# Canhbaochayrung.net
KiCad netlist of a schematic drawn in Altium Designer
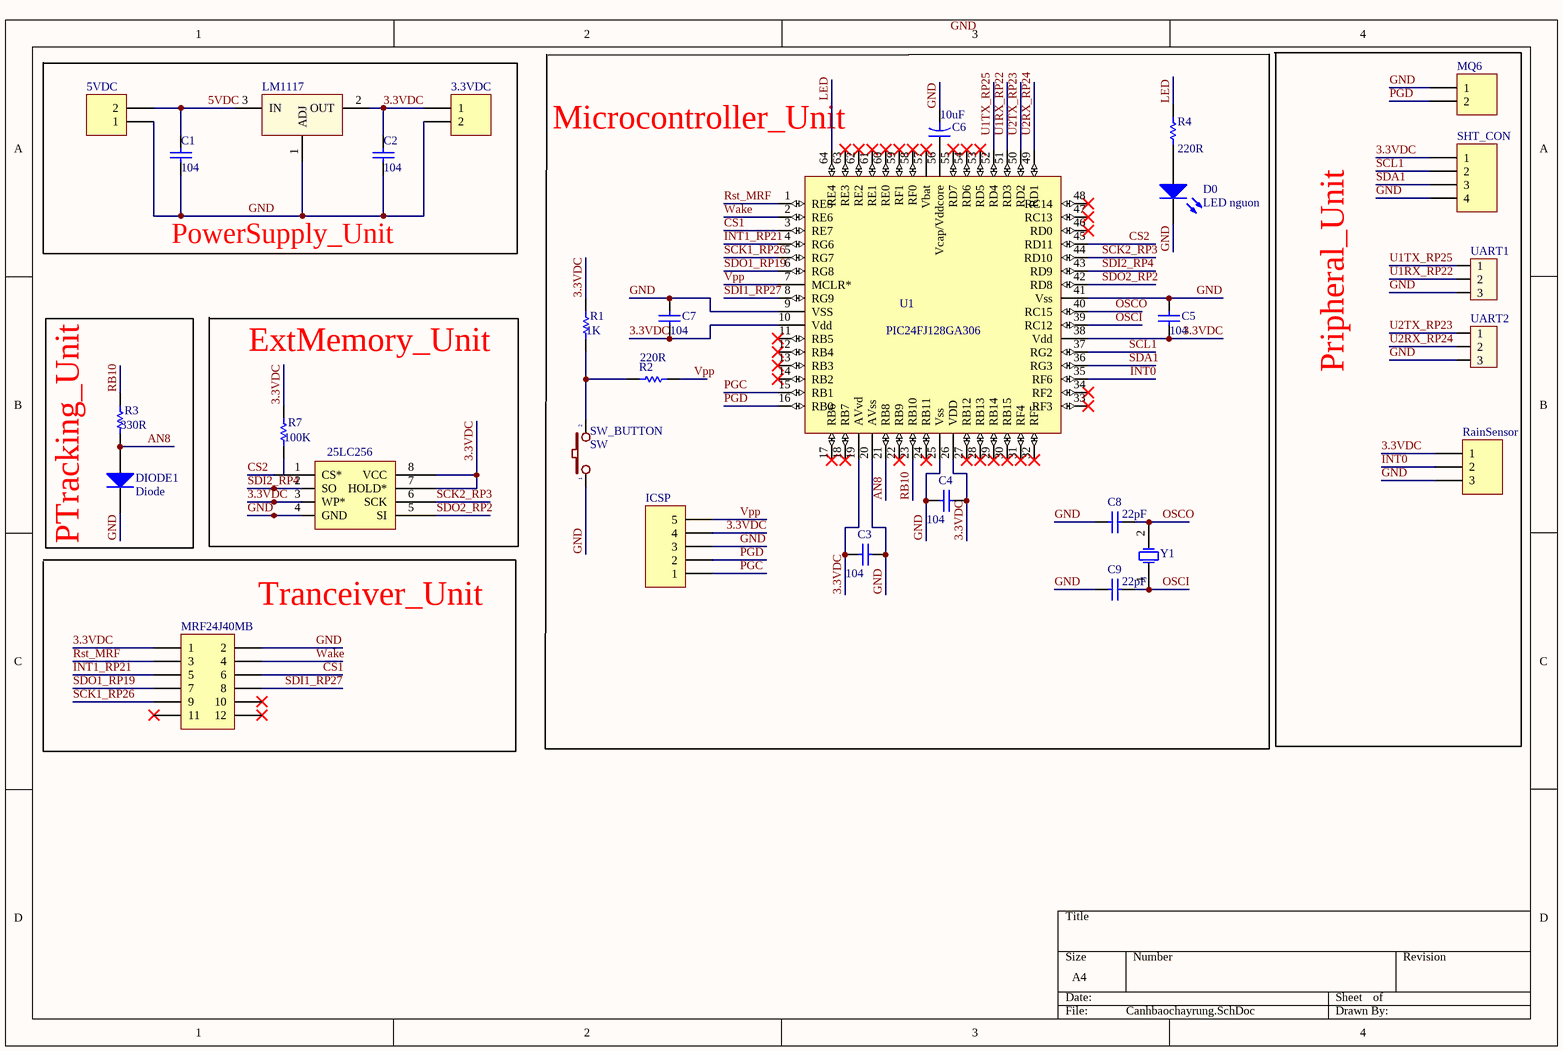
[diagram p0: Canhbaochayrung.SchDoc]

(export (version "E")
  (design (tool "Eeschema 10.0.6"))
  (components
    (comp (ref "3.3VDC")
      (value "Header 2")
      (footprint "HDR1X2")
      (description "Header, 2-Pin")
      (fields (field (name "PUBLISHER") "Altium Limited"))
      (libsource (lib "") (part "Header 2_1"))
    )
    (comp (ref "5VDC")
      (value "Header 2")
      (footprint "HDR1X2")
      (description "Header, 2-Pin")
      (fields (field (name "PUBLISHER") "Altium Limited"))
      (libsource (lib "Miscellaneous Connectors") (part "Header 2"))
    )
    (comp (ref "25LC256") (value "25LC256") (footprint "DIP-8") (libsource (lib "25LC256") (part "25LC256")))
    (comp (ref "C1")
      (value "104")
      (footprint "C0805")
      (description "Capacitor")
      (fields (field (name "Comment") "Cap") (field (name "PUBLISHER") "Altium Limited"))
      (libsource (lib "Miscellaneous Devices") (part "Cap"))
    )
    (comp (ref "C2")
      (value "104")
      (footprint "C0805")
      (description "Capacitor")
      (fields (field (name "Comment") "Cap") (field (name "PUBLISHER") "Altium Limited"))
      (libsource (lib "Miscellaneous Devices") (part "Cap"))
    )
    (comp (ref "C3")
      (value "104")
      (footprint "C0805")
      (description "Capacitor")
      (fields (field (name "Comment") "Cap") (field (name "PUBLISHER") "Altium Limited"))
      (libsource (lib "Miscellaneous Devices") (part "Cap"))
    )
    (comp (ref "C4")
      (value "104")
      (footprint "C0805")
      (description "Capacitor")
      (fields (field (name "Comment") "Cap") (field (name "PUBLISHER") "Altium Limited"))
      (libsource (lib "Miscellaneous Devices") (part "Cap"))
    )
    (comp (ref "C5")
      (value "104")
      (footprint "C0805")
      (description "Capacitor")
      (fields (field (name "Comment") "Cap") (field (name "PUBLISHER") "Altium Limited"))
      (libsource (lib "Miscellaneous Devices") (part "Cap"))
    )
    (comp (ref "C6")
      (value "10uF")
      (footprint "CAP P 6.3x5.4")
      (description "Capacitor")
      (fields (field (name "Comment") "Cap2") (field (name "PUBLISHER") "Altium Limited"))
      (libsource (lib "Miscellaneous Devices") (part "Cap2"))
    )
    (comp (ref "C7")
      (value "104")
      (footprint "C0805")
      (description "Capacitor")
      (fields (field (name "Comment") "Cap") (field (name "PUBLISHER") "Altium Limited"))
      (libsource (lib "Miscellaneous Devices") (part "Cap"))
    )
    (comp (ref "C8")
      (value "22pF")
      (footprint "SM-0805")
      (description "Capacitor")
      (fields (field (name "Comment") "Cap") (field (name "PUBLISHER") "Altium Limited"))
      (libsource (lib "Miscellaneous Devices") (part "Cap"))
    )
    (comp (ref "C9")
      (value "22pF")
      (footprint "SM-0805")
      (description "Capacitor")
      (fields (field (name "Comment") "Cap") (field (name "PUBLISHER") "Altium Limited"))
      (libsource (lib "Miscellaneous Devices") (part "Cap"))
    )
    (comp (ref "D0")
      (value "LED nguon")
      (footprint "LED3mm")
      (description "Typical INFRARED GaAs LED")
      (fields (field (name "PUBLISHER") "Altium Limited"))
      (libsource (lib "Miscellaneous Devices") (part "LED0"))
    )
    (comp (ref "DIODE1")
      (value "Diode")
      (footprint "DZ0.5A")
      (description "Default Diode")
      (fields (field (name "PUBLISHER") "Altium Limited"))
      (libsource (lib "Miscellaneous Devices") (part "Diode"))
    )
    (comp (ref "ICSP")
      (value "ICSP")
      (footprint "CON5")
      (description "Header, 5-Pin")
      (fields (field (name "PUBLISHER") "Altium Limited"))
      (libsource (lib "Miscellaneous Connectors") (part "Header 5"))
    )
    (comp (ref "LM1117")
      (value "LM317")
      (footprint "SOT223-4N")
      (description "Adj Voltage +1.2 -> +37V")
      (libsource (lib "syhaunguyen") (part "LM317"))
    )
    (comp (ref "MQ6")
      (value "MQ-6")
      (footprint "CON2")
      (description "Header, 2-Pin")
      (fields (field (name "PUBLISHER") "Altium Limited"))
      (libsource (lib "") (part "Header 2_1"))
    )
    (comp (ref "MRF24J40MB")
      (value "Header 6X2")
      (footprint "MRF24J40MB_board_mini")
      (description "Header, 6-Pin, Dual row")
      (fields (field (name "PUBLISHER") "Altium Limited"))
      (libsource (lib "Miscellaneous Connectors") (part "Header 6X2"))
    )
    (comp (ref "R1")
      (value "1K")
      (footprint "C0805")
      (description "Resistor")
      (fields (field (name "Comment") "Res1") (field (name "PUBLISHER") "Altium Limited"))
      (libsource (lib "Miscellaneous Devices") (part "Res1"))
    )
    (comp (ref "R2")
      (value "220R")
      (footprint "C0805")
      (description "Resistor")
      (fields (field (name "Comment") "res") (field (name "PUBLISHER") "Altium Limited"))
      (libsource (lib "Miscellaneous Devices") (part "Res1"))
    )
    (comp (ref "R3")
      (value "330R")
      (footprint "C0805")
      (description "Resistor")
      (fields (field (name "Comment") "Res1") (field (name "PUBLISHER") "Altium Limited"))
      (libsource (lib "Miscellaneous Devices") (part "Res1"))
    )
    (comp (ref "R4")
      (value "220R")
      (footprint "C0805")
      (description "Resistor")
      (fields (field (name "Comment") "Res1") (field (name "PUBLISHER") "Altium Limited"))
      (libsource (lib "Miscellaneous Devices") (part "Res1"))
    )
    (comp (ref "R7")
      (value "100K")
      (footprint "C0805")
      (description "Semiconductor Resistor")
      (fields (field (name "Comment") "Res Semi") (field (name "PUBLISHER") "Altium Limited"))
      (libsource (lib "Miscellaneous Devices") (part "Res Semi"))
    )
    (comp (ref "RainSensor")
      (value "PIR module")
      (footprint "CON3")
      (description "Header, 3-Pin, Right Angle")
      (fields (field (name "PUBLISHER") "Altium Limited"))
      (libsource (lib "Miscellaneous Connectors") (part "Header 3H"))
    )
    (comp (ref "SHT_CON")
      (value "SHT10 conector")
      (footprint "CON4")
      (description "Header, 4-Pin")
      (fields (field (name "PUBLISHER") "Altium Limited"))
      (libsource (lib "Miscellaneous Connectors") (part "Header 4"))
    )
    (comp (ref "SW_BUTTON")
      (value "SW")
      (footprint "SW-2P-S")
      (description "Switch button 2 pin")
      (libsource (lib "syhaunguyen") (part "SW2"))
    )
    (comp (ref "U1")
      (value "PIC24FJ128GA306")
      (footprint "TQFP-PT64_N")
      (libsource (lib "Mylibbrary") (part "PIC24FJ128GA306"))
    )
    (comp (ref "UART1")
      (value "UART1")
      (footprint "CON3")
      (description "Connector 3")
      (libsource (lib "syhaunguyen") (part "Con3"))
    )
    (comp (ref "UART2")
      (value "UART2")
      (footprint "CON3")
      (description "Connector 3")
      (libsource (lib "syhaunguyen") (part "Con3"))
    )
    (comp (ref "Y1")
      (value "XTAL")
      (footprint "XT2")
      (description "Crystal Oscillator")
      (fields (field (name "PUBLISHER") "Altium Limited"))
      (libsource (lib "Miscellaneous Devices") (part "XTAL"))
    )
  )
  (nets
    (net (code "1") (name "/3.3VDC") (class "Default")
      (node (ref "25LC256") (pin "3") (pinfunction "WP*_3") (pintype "passive"))
      (node (ref "25LC256") (pin "7") (pinfunction "HOLD*_7") (pintype "passive"))
      (node (ref "25LC256") (pin "8") (pinfunction "VCC_8") (pintype "power_in"))
      (node (ref "3.3VDC") (pin "1") (pinfunction "1_1") (pintype "passive"))
      (node (ref "C2") (pin "2") (pinfunction "2_2") (pintype "passive"))
      (node (ref "C3") (pin "1") (pinfunction "1_1") (pintype "passive"))
      (node (ref "C4") (pin "2") (pinfunction "2_2") (pintype "passive"))
      (node (ref "C5") (pin "1") (pinfunction "1_1") (pintype "passive"))
      (node (ref "C7") (pin "1") (pinfunction "1_1") (pintype "passive"))
      (node (ref "ICSP") (pin "4") (pinfunction "4_4") (pintype "passive"))
      (node (ref "LM1117") (pin "2") (pinfunction "OUT_2") (pintype "passive"))
      (node (ref "MRF24J40MB") (pin "1") (pinfunction "1_1") (pintype "passive"))
      (node (ref "R1") (pin "2") (pinfunction "2_2") (pintype "passive"))
      (node (ref "R7") (pin "2") (pinfunction "2_2") (pintype "passive"))
      (node (ref "RainSensor") (pin "1") (pinfunction "1_1") (pintype "passive"))
      (node (ref "SHT_CON") (pin "1") (pinfunction "1_1") (pintype "passive"))
      (node (ref "U1") (pin "10") (pinfunction "Vdd_10") (pintype "passive"))
      (node (ref "U1") (pin "19") (pinfunction "AVvd_19") (pintype "power_in"))
      (node (ref "U1") (pin "26") (pinfunction "VDD_26") (pintype "power_in"))
      (node (ref "U1") (pin "38") (pinfunction "Vdd_38") (pintype "power_in"))
    )
    (net (code "2") (name "/5VDC") (class "Default")
      (node (ref "5VDC") (pin "2") (pinfunction "2_2") (pintype "passive"))
      (node (ref "C1") (pin "2") (pinfunction "2_2") (pintype "passive"))
      (node (ref "LM1117") (pin "3") (pinfunction "IN_3") (pintype "passive"))
    )
    (net (code "3") (name "/AN8") (class "Default")
      (node (ref "DIODE1") (pin "1") (pinfunction "A_1") (pintype "passive"))
      (node (ref "R3") (pin "1") (pinfunction "1_1") (pintype "passive"))
      (node (ref "U1") (pin "21") (pinfunction "RB8_21") (pintype "bidirectional"))
    )
    (net (code "4") (name "/CS1") (class "Default")
      (node (ref "MRF24J40MB") (pin "6") (pinfunction "6_6") (pintype "passive"))
      (node (ref "U1") (pin "3") (pinfunction "RE7_3") (pintype "bidirectional"))
    )
    (net (code "5") (name "/CS2") (class "Default")
      (node (ref "25LC256") (pin "1") (pinfunction "CS*_1") (pintype "passive"))
      (node (ref "U1") (pin "45") (pinfunction "RD11_45") (pintype "bidirectional"))
    )
    (net (code "6") (name "/GND") (class "Default")
      (node (ref "25LC256") (pin "4") (pinfunction "GND_4") (pintype "power_in"))
      (node (ref "3.3VDC") (pin "2") (pinfunction "2_2") (pintype "passive"))
      (node (ref "5VDC") (pin "1") (pinfunction "1_1") (pintype "passive"))
      (node (ref "C1") (pin "1") (pinfunction "1_1") (pintype "passive"))
      (node (ref "C2") (pin "1") (pinfunction "1_1") (pintype "passive"))
      (node (ref "C3") (pin "2") (pinfunction "2_2") (pintype "passive"))
      (node (ref "C4") (pin "1") (pinfunction "1_1") (pintype "passive"))
      (node (ref "C5") (pin "2") (pinfunction "2_2") (pintype "passive"))
      (node (ref "C6") (pin "2") (pinfunction "2_2") (pintype "passive"))
      (node (ref "C7") (pin "2") (pinfunction "2_2") (pintype "passive"))
      (node (ref "C8") (pin "1") (pinfunction "1_1") (pintype "passive"))
      (node (ref "C9") (pin "1") (pinfunction "1_1") (pintype "passive"))
      (node (ref "D0") (pin "2") (pinfunction "K_2") (pintype "passive"))
      (node (ref "DIODE1") (pin "2") (pinfunction "K_2") (pintype "passive"))
      (node (ref "ICSP") (pin "3") (pinfunction "3_3") (pintype "passive"))
      (node (ref "LM1117") (pin "1") (pinfunction "ADJ_1") (pintype "passive"))
      (node (ref "MQ6") (pin "1") (pinfunction "1_1") (pintype "passive"))
      (node (ref "MRF24J40MB") (pin "2") (pinfunction "2_2") (pintype "passive"))
      (node (ref "RainSensor") (pin "3") (pinfunction "3_3") (pintype "passive"))
      (node (ref "SHT_CON") (pin "4") (pinfunction "4_4") (pintype "passive"))
      (node (ref "SW_BUTTON") (pin "1") (pinfunction "1_1") (pintype "passive"))
      (node (ref "U1") (pin "20") (pinfunction "AVss_20") (pintype "power_in"))
      (node (ref "U1") (pin "25") (pinfunction "Vss_25") (pintype "power_in"))
      (node (ref "U1") (pin "41") (pinfunction "Vss_41") (pintype "power_in"))
      (node (ref "U1") (pin "9") (pinfunction "VSS_9") (pintype "power_in"))
      (node (ref "UART1") (pin "3") (pinfunction "3_3") (pintype "passive"))
      (node (ref "UART2") (pin "3") (pinfunction "3_3") (pintype "passive"))
    )
    (net (code "7") (name "/INT0") (class "Default")
      (node (ref "RainSensor") (pin "2") (pinfunction "2_2") (pintype "passive"))
      (node (ref "U1") (pin "35") (pinfunction "RF6_35") (pintype "bidirectional"))
    )
    (net (code "8") (name "/INT1_RP21") (class "Default")
      (node (ref "MRF24J40MB") (pin "5") (pinfunction "5_5") (pintype "passive"))
      (node (ref "U1") (pin "4") (pinfunction "RG6_4") (pintype "bidirectional"))
    )
    (net (code "9") (name "/LED") (class "Default")
      (node (ref "R4") (pin "2") (pinfunction "2_2") (pintype "passive"))
      (node (ref "U1") (pin "64") (pinfunction "RE4_64") (pintype "bidirectional"))
    )
    (net (code "10") (name "/OSCI") (class "Default")
      (node (ref "C9") (pin "2") (pinfunction "2_2") (pintype "passive"))
      (node (ref "U1") (pin "39") (pinfunction "RC12_39") (pintype "bidirectional"))
      (node (ref "Y1") (pin "1") (pinfunction "OSC1_1") (pintype "passive"))
    )
    (net (code "11") (name "/OSCO") (class "Default")
      (node (ref "C8") (pin "2") (pinfunction "2_2") (pintype "passive"))
      (node (ref "U1") (pin "40") (pinfunction "RC15_40") (pintype "bidirectional"))
      (node (ref "Y1") (pin "2") (pinfunction "OSC2_2") (pintype "passive"))
    )
    (net (code "12") (name "/PGC") (class "Default")
      (node (ref "ICSP") (pin "1") (pinfunction "1_1") (pintype "passive"))
      (node (ref "U1") (pin "15") (pinfunction "RB1_15") (pintype "bidirectional"))
    )
    (net (code "13") (name "/PGD") (class "Default")
      (node (ref "ICSP") (pin "2") (pinfunction "2_2") (pintype "passive"))
      (node (ref "MQ6") (pin "2") (pinfunction "2_2") (pintype "passive"))
      (node (ref "U1") (pin "16") (pinfunction "RB0_16") (pintype "bidirectional"))
    )
    (net (code "14") (name "/RB10") (class "Default")
      (node (ref "R3") (pin "2") (pinfunction "2_2") (pintype "passive"))
      (node (ref "U1") (pin "23") (pinfunction "RB10_23") (pintype "bidirectional"))
    )
    (net (code "15") (name "/Rst_MRF") (class "Default")
      (node (ref "MRF24J40MB") (pin "3") (pinfunction "3_3") (pintype "passive"))
      (node (ref "U1") (pin "1") (pinfunction "RE5_1") (pintype "bidirectional"))
    )
    (net (code "16") (name "/SCK1_RP26") (class "Default")
      (node (ref "MRF24J40MB") (pin "9") (pinfunction "9_9") (pintype "passive"))
      (node (ref "U1") (pin "5") (pinfunction "RG7_5") (pintype "bidirectional"))
    )
    (net (code "17") (name "/SCK2_RP3") (class "Default")
      (node (ref "25LC256") (pin "6") (pinfunction "SCK_6") (pintype "passive"))
      (node (ref "U1") (pin "44") (pinfunction "RD10_44") (pintype "bidirectional"))
    )
    (net (code "18") (name "/SCL1") (class "Default")
      (node (ref "SHT_CON") (pin "2") (pinfunction "2_2") (pintype "passive"))
      (node (ref "U1") (pin "37") (pinfunction "RG2_37") (pintype "bidirectional"))
    )
    (net (code "19") (name "/SDA1") (class "Default")
      (node (ref "SHT_CON") (pin "3") (pinfunction "3_3") (pintype "passive"))
      (node (ref "U1") (pin "36") (pinfunction "RG3_36") (pintype "bidirectional"))
    )
    (net (code "20") (name "/SDI1_RP27") (class "Default")
      (node (ref "MRF24J40MB") (pin "8") (pinfunction "8_8") (pintype "passive"))
      (node (ref "U1") (pin "8") (pinfunction "RG9_8") (pintype "bidirectional"))
    )
    (net (code "21") (name "/SDI2_RP4") (class "Default")
      (node (ref "25LC256") (pin "2") (pinfunction "SO_2") (pintype "passive"))
      (node (ref "U1") (pin "43") (pinfunction "RD9_43") (pintype "bidirectional"))
    )
    (net (code "22") (name "/SDO1_RP19") (class "Default")
      (node (ref "MRF24J40MB") (pin "7") (pinfunction "7_7") (pintype "passive"))
      (node (ref "U1") (pin "6") (pinfunction "RG8_6") (pintype "bidirectional"))
    )
    (net (code "23") (name "/SDO2_RP2") (class "Default")
      (node (ref "25LC256") (pin "5") (pinfunction "SI_5") (pintype "passive"))
      (node (ref "U1") (pin "42") (pinfunction "RD8_42") (pintype "bidirectional"))
    )
    (net (code "24") (name "/U1RX_RP22") (class "Default")
      (node (ref "U1") (pin "51") (pinfunction "RD3_51") (pintype "bidirectional"))
      (node (ref "UART1") (pin "2") (pinfunction "2_2") (pintype "passive"))
    )
    (net (code "25") (name "/U1TX_RP25") (class "Default")
      (node (ref "U1") (pin "52") (pinfunction "RD4_52") (pintype "bidirectional"))
      (node (ref "UART1") (pin "1") (pinfunction "1_1") (pintype "passive"))
    )
    (net (code "26") (name "/U2RX_RP24") (class "Default")
      (node (ref "U1") (pin "49") (pinfunction "RD1_49") (pintype "bidirectional"))
      (node (ref "UART2") (pin "2") (pinfunction "2_2") (pintype "passive"))
    )
    (net (code "27") (name "/U2TX_RP23") (class "Default")
      (node (ref "U1") (pin "50") (pinfunction "RD2_50") (pintype "bidirectional"))
      (node (ref "UART2") (pin "1") (pinfunction "1_1") (pintype "passive"))
    )
    (net (code "28") (name "/Vpp") (class "Default")
      (node (ref "ICSP") (pin "5") (pinfunction "5_5") (pintype "passive"))
      (node (ref "R2") (pin "2") (pinfunction "2_2") (pintype "passive"))
      (node (ref "U1") (pin "7") (pinfunction "MCLR*_7") (pintype "passive"))
    )
    (net (code "29") (name "/Wake") (class "Default")
      (node (ref "MRF24J40MB") (pin "4") (pinfunction "4_4") (pintype "passive"))
      (node (ref "U1") (pin "2") (pinfunction "RE6_2") (pintype "bidirectional"))
    )
    (net (code "30") (name "Net-(D0-A)") (class "Default")
      (node (ref "D0") (pin "1") (pinfunction "A_1") (pintype "passive"))
      (node (ref "R4") (pin "1") (pinfunction "1_1") (pintype "passive"))
    )
    (net (code "31") (name "Net-(R1-Pad1)") (class "Default")
      (node (ref "R1") (pin "1") (pinfunction "1_1") (pintype "passive"))
      (node (ref "R2") (pin "1") (pinfunction "1_1") (pintype "passive"))
      (node (ref "SW_BUTTON") (pin "2") (pinfunction "2_2") (pintype "passive"))
    )
    (net (code "32") (name "Net-(U1-Vcap{slash}Vddcore)") (class "Default")
      (node (ref "C6") (pin "1") (pinfunction "1_1") (pintype "passive"))
      (node (ref "U1") (pin "56") (pinfunction "Vcap/Vddcore_56") (pintype "power_in"))
    )
    (net (code "33") (name "unconnected-(MRF24J40MB-Pad10)") (class "Default")
      (node (ref "MRF24J40MB") (pin "10") (pinfunction "10_10") (pintype "passive+no_connect"))
    )
    (net (code "34") (name "unconnected-(MRF24J40MB-Pad11)") (class "Default")
      (node (ref "MRF24J40MB") (pin "11") (pinfunction "11_11") (pintype "passive+no_connect"))
    )
    (net (code "35") (name "unconnected-(MRF24J40MB-Pad12)") (class "Default")
      (node (ref "MRF24J40MB") (pin "12") (pinfunction "12_12") (pintype "passive+no_connect"))
    )
    (net (code "36") (name "unconnected-(R7-Pad1)") (class "Default")
      (node (ref "R7") (pin "1") (pinfunction "1_1") (pintype "passive"))
    )
    (net (code "37") (name "unconnected-(U1-RB2-Pad14)") (class "Default")
      (node (ref "U1") (pin "14") (pinfunction "RB2_14") (pintype "bidirectional+no_connect"))
    )
    (net (code "38") (name "unconnected-(U1-RB3-Pad13)") (class "Default")
      (node (ref "U1") (pin "13") (pinfunction "RB3_13") (pintype "bidirectional+no_connect"))
    )
    (net (code "39") (name "unconnected-(U1-RB4-Pad12)") (class "Default")
      (node (ref "U1") (pin "12") (pinfunction "RB4_12") (pintype "bidirectional+no_connect"))
    )
    (net (code "40") (name "unconnected-(U1-RB5-Pad11)") (class "Default")
      (node (ref "U1") (pin "11") (pinfunction "RB5_11") (pintype "bidirectional+no_connect"))
    )
    (net (code "41") (name "unconnected-(U1-RB6-Pad17)") (class "Default")
      (node (ref "U1") (pin "17") (pinfunction "RB6_17") (pintype "bidirectional+no_connect"))
    )
    (net (code "42") (name "unconnected-(U1-RB7-Pad18)") (class "Default")
      (node (ref "U1") (pin "18") (pinfunction "RB7_18") (pintype "bidirectional+no_connect"))
    )
    (net (code "43") (name "unconnected-(U1-RB9-Pad22)") (class "Default")
      (node (ref "U1") (pin "22") (pinfunction "RB9_22") (pintype "bidirectional+no_connect"))
    )
    (net (code "44") (name "unconnected-(U1-RB11-Pad24)") (class "Default")
      (node (ref "U1") (pin "24") (pinfunction "RB11_24") (pintype "bidirectional+no_connect"))
    )
    (net (code "45") (name "unconnected-(U1-RB12-Pad27)") (class "Default")
      (node (ref "U1") (pin "27") (pinfunction "RB12_27") (pintype "bidirectional+no_connect"))
    )
    (net (code "46") (name "unconnected-(U1-RB13-Pad28)") (class "Default")
      (node (ref "U1") (pin "28") (pinfunction "RB13_28") (pintype "bidirectional+no_connect"))
    )
    (net (code "47") (name "unconnected-(U1-RB14-Pad29)") (class "Default")
      (node (ref "U1") (pin "29") (pinfunction "RB14_29") (pintype "bidirectional+no_connect"))
    )
    (net (code "48") (name "unconnected-(U1-RB15-Pad30)") (class "Default")
      (node (ref "U1") (pin "30") (pinfunction "RB15_30") (pintype "bidirectional+no_connect"))
    )
    (net (code "49") (name "unconnected-(U1-RC13-Pad47)") (class "Default")
      (node (ref "U1") (pin "47") (pinfunction "RC13_47") (pintype "bidirectional+no_connect"))
    )
    (net (code "50") (name "unconnected-(U1-RC14-Pad48)") (class "Default")
      (node (ref "U1") (pin "48") (pinfunction "RC14_48") (pintype "bidirectional+no_connect"))
    )
    (net (code "51") (name "unconnected-(U1-RD0-Pad46)") (class "Default")
      (node (ref "U1") (pin "46") (pinfunction "RD0_46") (pintype "bidirectional+no_connect"))
    )
    (net (code "52") (name "unconnected-(U1-RD5-Pad53)") (class "Default")
      (node (ref "U1") (pin "53") (pinfunction "RD5_53") (pintype "bidirectional+no_connect"))
    )
    (net (code "53") (name "unconnected-(U1-RD6-Pad54)") (class "Default")
      (node (ref "U1") (pin "54") (pinfunction "RD6_54") (pintype "bidirectional+no_connect"))
    )
    (net (code "54") (name "unconnected-(U1-RD7-Pad55)") (class "Default")
      (node (ref "U1") (pin "55") (pinfunction "RD7_55") (pintype "bidirectional+no_connect"))
    )
    (net (code "55") (name "unconnected-(U1-RE0-Pad60)") (class "Default")
      (node (ref "U1") (pin "60") (pinfunction "RE0_60") (pintype "bidirectional+no_connect"))
    )
    (net (code "56") (name "unconnected-(U1-RE1-Pad61)") (class "Default")
      (node (ref "U1") (pin "61") (pinfunction "RE1_61") (pintype "bidirectional+no_connect"))
    )
    (net (code "57") (name "unconnected-(U1-RE2-Pad62)") (class "Default")
      (node (ref "U1") (pin "62") (pinfunction "RE2_62") (pintype "bidirectional+no_connect"))
    )
    (net (code "58") (name "unconnected-(U1-RE3-Pad63)") (class "Default")
      (node (ref "U1") (pin "63") (pinfunction "RE3_63") (pintype "bidirectional+no_connect"))
    )
    (net (code "59") (name "unconnected-(U1-RF0-Pad58)") (class "Default")
      (node (ref "U1") (pin "58") (pinfunction "RF0_58") (pintype "bidirectional+no_connect"))
    )
    (net (code "60") (name "unconnected-(U1-RF1-Pad59)") (class "Default")
      (node (ref "U1") (pin "59") (pinfunction "RF1_59") (pintype "bidirectional+no_connect"))
    )
    (net (code "61") (name "unconnected-(U1-RF2-Pad34)") (class "Default")
      (node (ref "U1") (pin "34") (pinfunction "RF2_34") (pintype "bidirectional+no_connect"))
    )
    (net (code "62") (name "unconnected-(U1-RF3-Pad33)") (class "Default")
      (node (ref "U1") (pin "33") (pinfunction "RF3_33") (pintype "bidirectional+no_connect"))
    )
    (net (code "63") (name "unconnected-(U1-RF4-Pad31)") (class "Default")
      (node (ref "U1") (pin "31") (pinfunction "RF4_31") (pintype "bidirectional+no_connect"))
    )
    (net (code "64") (name "unconnected-(U1-RF5-Pad32)") (class "Default")
      (node (ref "U1") (pin "32") (pinfunction "RF5_32") (pintype "bidirectional+no_connect"))
    )
    (net (code "65") (name "unconnected-(U1-Vbat-Pad57)") (class "Default")
      (node (ref "U1") (pin "57") (pinfunction "Vbat_57") (pintype "power_in+no_connect"))
    )
  )
)
